# USB-C.net
KiCad netlist of a schematic drawn in Altium Designer
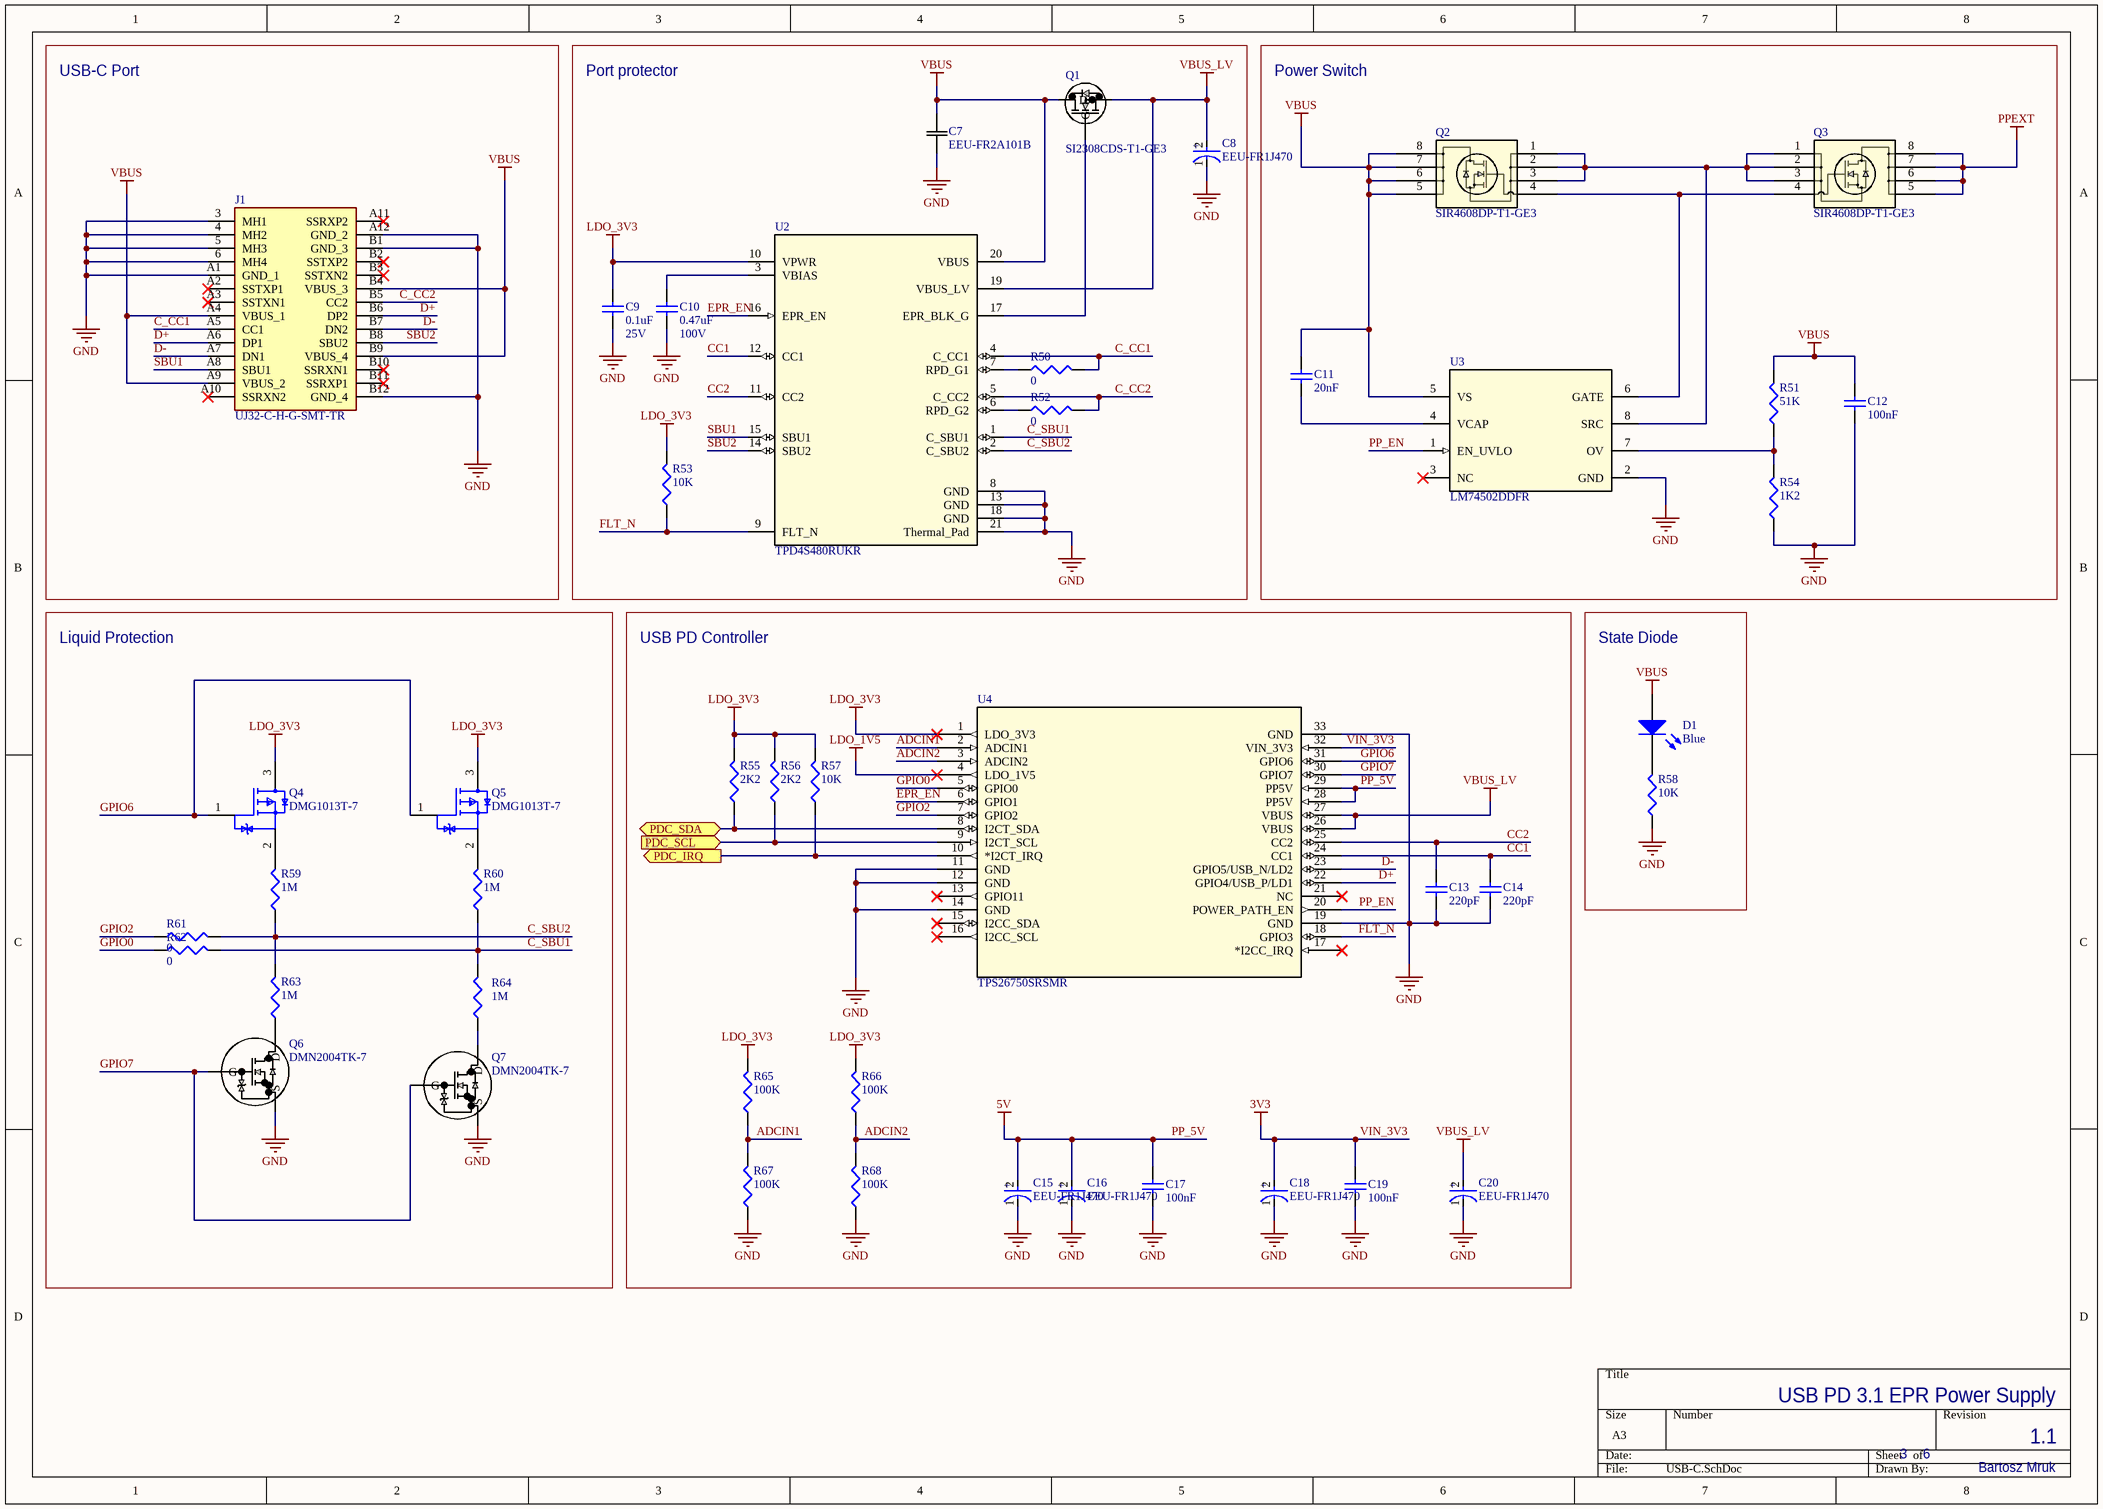
[diagram p0: USB-C.SchDoc]

(export (version "E")
  (design (tool "Eeschema 10.0.6"))
  (components
    (comp (ref "C7")
      (value "EEU-FR2A101B")
      (footprint "CAP_EEU-FR2A101B_PAN")
      (description "No Description Available")
      (fields (field (name "COPYRIGHT") "Copyright (C) 2025 Ultra Librarian. All rights reserved."))
      (libsource (lib "EEU-FR2A101B") (part "EEU-FR2A101B"))
    )
    (comp (ref "C8")
      (value "EEU-FR1J470")
      (footprint "FP-EEU-FR1J470-MFG")
      (description "CAP ALUM 47UF 20% 63V RADIAL")
      (fields (field (name "TOLERANCE") "20%") (field (name "VOLTAGE") "63V"))
      (libsource (lib "Altium Content Vault") (part "203bc49f2ac43e59fd269a8c329ed05"))
    )
    (comp (ref "C9")
      (value "25V")
      (footprint "C1206")
      (description "Capacitor (Semiconductor SIM Model)")
      (fields (field (name "ALTIUM_VALUE") "0.1uF") (field (name "PUBLISHER") "Altium Limited"))
      (libsource (lib "Miscellaneous Devices") (part "Cap Semi"))
    )
    (comp (ref "C10")
      (value "100V")
      (footprint "C1206")
      (description "Capacitor (Semiconductor SIM Model)")
      (fields (field (name "ALTIUM_VALUE") "0.47uF") (field (name "PUBLISHER") "Altium Limited"))
      (libsource (lib "Miscellaneous Devices") (part "Cap Semi"))
    )
    (comp (ref "C11")
      (value "20nF")
      (footprint "C1206")
      (description "Capacitor (Semiconductor SIM Model)")
      (fields (field (name "Comment") "at least 13V") (field (name "PUBLISHER") "Altium Limited"))
      (libsource (lib "Miscellaneous Devices") (part "Cap Semi"))
    )
    (comp (ref "C12")
      (value "100nF")
      (footprint "C1206")
      (description "Capacitor (Semiconductor SIM Model)")
      (fields (field (name "Comment") "Cap Semi") (field (name "PUBLISHER") "Altium Limited"))
      (libsource (lib "Miscellaneous Devices") (part "Cap Semi"))
    )
    (comp (ref "C13")
      (value "220pF")
      (footprint "0402")
      (description "Capacitor (Semiconductor SIM Model)")
      (fields (field (name "Comment") "Cap Semi") (field (name "PUBLISHER") "Altium Limited"))
      (libsource (lib "Miscellaneous Devices") (part "Cap Semi"))
    )
    (comp (ref "C14")
      (value "220pF")
      (footprint "0402")
      (description "Capacitor (Semiconductor SIM Model)")
      (fields (field (name "Comment") "Cap Semi") (field (name "PUBLISHER") "Altium Limited"))
      (libsource (lib "Miscellaneous Devices") (part "Cap Semi"))
    )
    (comp (ref "C15")
      (value "EEU-FR1J470")
      (footprint "FP-EEU-FR1J470-MFG")
      (description "CAP ALUM 47UF 20% 63V RADIAL")
      (fields (field (name "TOLERANCE") "20%") (field (name "VOLTAGE") "63V"))
      (libsource (lib "Altium Content Vault") (part "203bc49f2ac43e59fd269a8c329ed05"))
    )
    (comp (ref "C16")
      (value "EEU-FR1J470")
      (footprint "FP-EEU-FR1J470-MFG")
      (description "CAP ALUM 47UF 20% 63V RADIAL")
      (fields (field (name "TOLERANCE") "20%") (field (name "VOLTAGE") "63V"))
      (libsource (lib "Altium Content Vault") (part "203bc49f2ac43e59fd269a8c329ed05"))
    )
    (comp (ref "C17")
      (value "100nF")
      (footprint "C1206")
      (description "Capacitor (Semiconductor SIM Model)")
      (fields (field (name "Comment") "Cap Semi") (field (name "PUBLISHER") "Altium Limited"))
      (libsource (lib "Miscellaneous Devices") (part "Cap Semi"))
    )
    (comp (ref "C18")
      (value "EEU-FR1J470")
      (footprint "FP-EEU-FR1J470-MFG")
      (description "CAP ALUM 47UF 20% 63V RADIAL")
      (fields (field (name "TOLERANCE") "20%") (field (name "VOLTAGE") "63V"))
      (libsource (lib "Altium Content Vault") (part "203bc49f2ac43e59fd269a8c329ed05"))
    )
    (comp (ref "C19")
      (value "100nF")
      (footprint "C1206")
      (description "Capacitor (Semiconductor SIM Model)")
      (fields (field (name "Comment") "Cap Semi") (field (name "PUBLISHER") "Altium Limited"))
      (libsource (lib "Miscellaneous Devices") (part "Cap Semi"))
    )
    (comp (ref "C20")
      (value "EEU-FR1J470")
      (footprint "FP-EEU-FR1J470-MFG")
      (description "CAP ALUM 47UF 20% 63V RADIAL")
      (fields (field (name "TOLERANCE") "20%") (field (name "VOLTAGE") "63V"))
      (libsource (lib "Altium Content Vault") (part "203bc49f2ac43e59fd269a8c329ed05"))
    )
    (comp (ref "D1")
      (value "Blue")
      (footprint "3.2X1.6X1.1")
      (description "Typical RED, GREEN, YELLOW, AMBER GaAs LED")
      (fields (field (name "PUBLISHER") "Altium Limited"))
      (libsource (lib "Miscellaneous Devices") (part "LED2"))
    )
    (comp (ref "J1")
      (value "UJ32-C-H-G-SMT-TR")
      (footprint "UJ32CHGSMTTR")
      (fields (field (name "MOUSER PART NUMBER") "179-UJ32CHGSMTTR"))
      (libsource (lib "UJ32-C-H-G-SMT-TR") (part "UJ32-C-H-G-SMT-TR"))
    )
    (comp (ref "Q1")
      (value "SI2308CDS-T1-GE3")
      (footprint "SOT-23_TO-236_VIS")
      (description "N-CHANNEL 60-V (D-S) MOSFET")
      (fields (field (name "COPYRIGHT") "Copyright (C) 2025 Ultra Librarian. All rights reserved."))
      (libsource (lib "SI2308CDS-T1-GE3") (part "SI2308CDS-T1-GE3"))
    )
    (comp (ref "Q2")
      (value "SIR4608DP-T1-GE3")
      (footprint "POWERPAK_SO-8_SINGLE_VIS")
      (description "N-CHANNEL 60-V (D-S) MOSFET")
      (fields (field (name "COPYRIGHT") "Copyright (C) 2025 Ultra Librarian. All rights reserved."))
      (libsource (lib "SIR4608DP-T1-GE3") (part "SIR4608DP-T1-GE3"))
    )
    (comp (ref "Q3")
      (value "SIR4608DP-T1-GE3")
      (footprint "POWERPAK_SO-8_SINGLE_VIS")
      (description "N-CHANNEL 60-V (D-S) MOSFET")
      (fields (field (name "COPYRIGHT") "Copyright (C) 2025 Ultra Librarian. All rights reserved."))
      (libsource (lib "SIR4608DP-T1-GE3") (part "SIR4608DP-T1-GE3"))
    )
    (comp (ref "Q4")
      (value "DMG1013T-7")
      (footprint "FP-SOT523-IPC_A")
      (description "MOSFET P-CH 20V 0.46A SOT-523")
      (libsource (lib "Altium Content Vault") (part "d2c0d31e441d0c4ace7f3b05f74b3be"))
    )
    (comp (ref "Q5")
      (value "DMG1013T-7")
      (footprint "FP-SOT523-IPC_A")
      (description "MOSFET P-CH 20V 0.46A SOT-523")
      (libsource (lib "Altium Content Vault") (part "d2c0d31e441d0c4ace7f3b05f74b3be"))
    )
    (comp (ref "Q6")
      (value "DMN2004TK-7")
      (footprint "SOT523_DMN2004_DIO")
      (description "Description")
      (fields (field (name "COPYRIGHT") "Copyright (C) 2025 Ultra Librarian. All rights reserved."))
      (libsource (lib "DMN2004TK-7") (part "DMN2004TK-7"))
    )
    (comp (ref "Q7")
      (value "DMN2004TK-7")
      (footprint "SOT523_DMN2004_DIO")
      (description "Description")
      (fields (field (name "COPYRIGHT") "Copyright (C) 2025 Ultra Librarian. All rights reserved."))
      (libsource (lib "DMN2004TK-7") (part "DMN2004TK-7"))
    )
    (comp (ref "R50")
      (value "0")
      (footprint "J1-0603")
      (description "Resistor")
      (fields (field (name "Comment") "Res3") (field (name "PUBLISHER") "Altium Limited"))
      (libsource (lib "Miscellaneous Devices") (part "Res3"))
    )
    (comp (ref "R51")
      (value "51K")
      (footprint "J1-0603")
      (description "Resistor")
      (fields (field (name "Comment") "Res3") (field (name "PUBLISHER") "Altium Limited"))
      (libsource (lib "Miscellaneous Devices") (part "Res3"))
    )
    (comp (ref "R52")
      (value "0")
      (footprint "J1-0603")
      (description "Resistor")
      (fields (field (name "Comment") "Res3") (field (name "PUBLISHER") "Altium Limited"))
      (libsource (lib "Miscellaneous Devices") (part "Res3"))
    )
    (comp (ref "R53")
      (value "10K")
      (footprint "J1-0603")
      (description "Resistor")
      (fields (field (name "Comment") "Res3") (field (name "PUBLISHER") "Altium Limited"))
      (libsource (lib "Miscellaneous Devices") (part "Res3"))
    )
    (comp (ref "R54")
      (value "1K2")
      (footprint "J1-0603")
      (description "Resistor")
      (fields (field (name "Comment") "Res3") (field (name "PUBLISHER") "Altium Limited"))
      (libsource (lib "Miscellaneous Devices") (part "Res3"))
    )
    (comp (ref "R55")
      (value "2K2")
      (footprint "J1-0603")
      (description "Resistor")
      (fields (field (name "Comment") "Res3") (field (name "PUBLISHER") "Altium Limited"))
      (libsource (lib "Miscellaneous Devices") (part "Res3"))
    )
    (comp (ref "R56")
      (value "2K2")
      (footprint "J1-0603")
      (description "Resistor")
      (fields (field (name "Comment") "Res3") (field (name "PUBLISHER") "Altium Limited"))
      (libsource (lib "Miscellaneous Devices") (part "Res3"))
    )
    (comp (ref "R57")
      (value "10K")
      (footprint "J1-0603")
      (description "Resistor")
      (fields (field (name "Comment") "Res3") (field (name "PUBLISHER") "Altium Limited"))
      (libsource (lib "Miscellaneous Devices") (part "Res3"))
    )
    (comp (ref "R58")
      (value "10K")
      (footprint "J1-0603")
      (description "Resistor")
      (fields (field (name "Comment") "Res3") (field (name "PUBLISHER") "Altium Limited"))
      (libsource (lib "Miscellaneous Devices") (part "Res3"))
    )
    (comp (ref "R59")
      (value "1M")
      (footprint "J1-0603")
      (description "Resistor")
      (fields (field (name "Comment") "Res3") (field (name "PUBLISHER") "Altium Limited"))
      (libsource (lib "Miscellaneous Devices") (part "Res3"))
    )
    (comp (ref "R60")
      (value "1M")
      (footprint "J1-0603")
      (description "Resistor")
      (fields (field (name "Comment") "Res3") (field (name "PUBLISHER") "Altium Limited"))
      (libsource (lib "Miscellaneous Devices") (part "Res3"))
    )
    (comp (ref "R61")
      (value "0")
      (footprint "J1-0603")
      (description "Resistor")
      (fields (field (name "Comment") "Res3") (field (name "PUBLISHER") "Altium Limited"))
      (libsource (lib "Miscellaneous Devices") (part "Res3"))
    )
    (comp (ref "R62")
      (value "0")
      (footprint "J1-0603")
      (description "Resistor")
      (fields (field (name "Comment") "Res3") (field (name "PUBLISHER") "Altium Limited"))
      (libsource (lib "Miscellaneous Devices") (part "Res3"))
    )
    (comp (ref "R63")
      (value "1M")
      (footprint "J1-0603")
      (description "Resistor")
      (fields (field (name "Comment") "Res3") (field (name "PUBLISHER") "Altium Limited"))
      (libsource (lib "Miscellaneous Devices") (part "Res3"))
    )
    (comp (ref "R64")
      (value "1M")
      (footprint "J1-0603")
      (description "Resistor")
      (fields (field (name "Comment") "Res3") (field (name "PUBLISHER") "Altium Limited"))
      (libsource (lib "Miscellaneous Devices") (part "Res3"))
    )
    (comp (ref "R65")
      (value "100K")
      (footprint "J1-0603")
      (description "Resistor")
      (fields (field (name "Comment") "Res3") (field (name "PUBLISHER") "Altium Limited"))
      (libsource (lib "Miscellaneous Devices") (part "Res3"))
    )
    (comp (ref "R66")
      (value "100K")
      (footprint "J1-0603")
      (description "Resistor")
      (fields (field (name "Comment") "Res3") (field (name "PUBLISHER") "Altium Limited"))
      (libsource (lib "Miscellaneous Devices") (part "Res3"))
    )
    (comp (ref "R67")
      (value "100K")
      (footprint "J1-0603")
      (description "Resistor")
      (fields (field (name "Comment") "Res3") (field (name "PUBLISHER") "Altium Limited"))
      (libsource (lib "Miscellaneous Devices") (part "Res3"))
    )
    (comp (ref "R68")
      (value "100K")
      (footprint "J1-0603")
      (description "Resistor")
      (fields (field (name "Comment") "Res3") (field (name "PUBLISHER") "Altium Limited"))
      (libsource (lib "Miscellaneous Devices") (part "Res3"))
    )
    (comp (ref "U2")
      (value "TPD4S480RUKR")
      (footprint "RUK0020B-IPC_A")
      (fields (field (name "COPYRIGHT") "Copyright (C) 2025 Ultra Librarian. All rights reserved."))
      (libsource (lib "TPD4S480RUKR") (part "TPD4S480RUKR"))
    )
    (comp (ref "U3")
      (value "LM74502DDFR")
      (footprint "DDF0008A-IPC_A")
      (description "3.2-V to 65-V industrial RPP controller with load disconnect and OVP 8-SOT-23-THIN -40 to 125")
      (fields (field (name "COPYRIGHT") "Copyright (C) 2025 Ultra Librarian. All rights reserved."))
      (libsource (lib "LM74502DDFR") (part "LM74502DDFR"))
    )
    (comp (ref "U4")
      (value "TPS26750SRSMR")
      (footprint "VQFN32_RSM_TEX")
      (fields (field (name "COPYRIGHT") "Copyright (C) 2025 Ultra Librarian. All rights reserved."))
      (libsource (lib "TPS26750SRSMR") (part "TPS26750SRSMR"))
    )
  )
  (nets
    (net (code "1") (name "/ADCIN1") (class "Default")
      (node (ref "R65") (pin "1") (pinfunction "1_1") (pintype "passive"))
      (node (ref "R67") (pin "2") (pinfunction "2_2") (pintype "passive"))
      (node (ref "U4") (pin "2") (pinfunction "ADCIN1_2") (pintype "input"))
    )
    (net (code "2") (name "/ADCIN2") (class "Default")
      (node (ref "R66") (pin "1") (pinfunction "1_1") (pintype "passive"))
      (node (ref "R68") (pin "2") (pinfunction "2_2") (pintype "passive"))
      (node (ref "U4") (pin "3") (pinfunction "ADCIN2_3") (pintype "input"))
    )
    (net (code "3") (name "/CC1") (class "Default")
      (node (ref "C14") (pin "2") (pinfunction "2_2") (pintype "passive"))
      (node (ref "U2") (pin "12") (pinfunction "CC1_12") (pintype "bidirectional"))
      (node (ref "U4") (pin "24") (pinfunction "CC1_24") (pintype "bidirectional"))
    )
    (net (code "4") (name "/CC2") (class "Default")
      (node (ref "C13") (pin "2") (pinfunction "2_2") (pintype "passive"))
      (node (ref "U2") (pin "11") (pinfunction "CC2_11") (pintype "bidirectional"))
      (node (ref "U4") (pin "25") (pinfunction "CC2_25") (pintype "bidirectional"))
    )
    (net (code "5") (name "/C_CC1") (class "Default")
      (node (ref "J1") (pin "A5") (pinfunction "CC1_A5") (pintype "passive"))
      (node (ref "R50") (pin "2") (pinfunction "2_2") (pintype "passive"))
      (node (ref "U2") (pin "4") (pinfunction "C_CC1_4") (pintype "bidirectional"))
    )
    (net (code "6") (name "/C_CC2") (class "Default")
      (node (ref "J1") (pin "B5") (pinfunction "CC2_B5") (pintype "passive"))
      (node (ref "R52") (pin "2") (pinfunction "2_2") (pintype "passive"))
      (node (ref "U2") (pin "5") (pinfunction "C_CC2_5") (pintype "bidirectional"))
    )
    (net (code "7") (name "/C_SBU1") (class "Default")
      (node (ref "R60") (pin "1") (pinfunction "1_1") (pintype "passive"))
      (node (ref "R62") (pin "2") (pinfunction "2_2") (pintype "passive"))
      (node (ref "R64") (pin "2") (pinfunction "2_2") (pintype "passive"))
      (node (ref "U2") (pin "1") (pinfunction "C_SBU1_1") (pintype "bidirectional"))
    )
    (net (code "8") (name "/C_SBU2") (class "Default")
      (node (ref "R59") (pin "1") (pinfunction "1_1") (pintype "passive"))
      (node (ref "R61") (pin "2") (pinfunction "2_2") (pintype "passive"))
      (node (ref "R63") (pin "2") (pinfunction "2_2") (pintype "passive"))
      (node (ref "U2") (pin "2") (pinfunction "C_SBU2_2") (pintype "bidirectional"))
    )
    (net (code "9") (name "/D+") (class "Default")
      (node (ref "J1") (pin "A6") (pinfunction "DP1_A6") (pintype "passive"))
      (node (ref "J1") (pin "B6") (pinfunction "DP2_B6") (pintype "passive"))
      (node (ref "U4") (pin "22") (pinfunction "GPIO4/USB_P/LD1_22") (pintype "bidirectional"))
    )
    (net (code "10") (name "/D-") (class "Default")
      (node (ref "J1") (pin "A7") (pinfunction "DN1_A7") (pintype "passive"))
      (node (ref "J1") (pin "B7") (pinfunction "DN2_B7") (pintype "passive"))
      (node (ref "U4") (pin "23") (pinfunction "GPIO5/USB_N/LD2_23") (pintype "bidirectional"))
    )
    (net (code "11") (name "/EPR_EN") (class "Default")
      (node (ref "U2") (pin "16") (pinfunction "EPR_EN_16") (pintype "input"))
      (node (ref "U4") (pin "6") (pinfunction "GPIO1_6") (pintype "bidirectional"))
    )
    (net (code "12") (name "/FLT_N") (class "Default")
      (node (ref "R53") (pin "1") (pinfunction "1_1") (pintype "passive"))
      (node (ref "U2") (pin "9") (pinfunction "FLT_N_9") (pintype "open_collector"))
      (node (ref "U4") (pin "18") (pinfunction "GPIO3_18") (pintype "bidirectional"))
    )
    (net (code "13") (name "/GPIO0") (class "Default")
      (node (ref "R62") (pin "1") (pinfunction "1_1") (pintype "passive"))
      (node (ref "U4") (pin "5") (pinfunction "GPIO0_5") (pintype "bidirectional"))
    )
    (net (code "14") (name "/GPIO2") (class "Default")
      (node (ref "R61") (pin "1") (pinfunction "1_1") (pintype "passive"))
      (node (ref "U4") (pin "7") (pinfunction "GPIO2_7") (pintype "bidirectional"))
    )
    (net (code "15") (name "/GPIO6") (class "Default")
      (node (ref "Q4") (pin "1") (pinfunction "G_1") (pintype "passive"))
      (node (ref "Q5") (pin "1") (pinfunction "G_1") (pintype "passive"))
      (node (ref "U4") (pin "31") (pinfunction "GPIO6_31") (pintype "bidirectional"))
    )
    (net (code "16") (name "/GPIO7") (class "Default")
      (node (ref "Q6") (pin "1") (pinfunction "G_1") (pintype "passive"))
      (node (ref "Q7") (pin "1") (pinfunction "G_1") (pintype "passive"))
      (node (ref "U4") (pin "30") (pinfunction "GPIO7_30") (pintype "bidirectional"))
    )
    (net (code "17") (name "/PDC_IRQ") (class "Default")
      (node (ref "R57") (pin "1") (pinfunction "1_1") (pintype "passive"))
      (node (ref "U4") (pin "10") (pinfunction "*I2CT_IRQ_10") (pintype "output"))
    )
    (net (code "18") (name "/PDC_SCL") (class "Default")
      (node (ref "R56") (pin "1") (pinfunction "1_1") (pintype "passive"))
      (node (ref "U4") (pin "9") (pinfunction "I2CT_SCL_9") (pintype "input"))
    )
    (net (code "19") (name "/PDC_SDA") (class "Default")
      (node (ref "R55") (pin "1") (pinfunction "1_1") (pintype "passive"))
      (node (ref "U4") (pin "8") (pinfunction "I2CT_SDA_8") (pintype "bidirectional"))
    )
    (net (code "20") (name "/PP_EN") (class "Default")
      (node (ref "U3") (pin "1") (pinfunction "EN_UVLO_1") (pintype "input"))
      (node (ref "U4") (pin "20") (pinfunction "POWER_PATH_EN_20") (pintype "output"))
    )
    (net (code "21") (name "/SBU1") (class "Default")
      (node (ref "J1") (pin "A8") (pinfunction "SBU1_A8") (pintype "passive"))
      (node (ref "U2") (pin "15") (pinfunction "SBU1_15") (pintype "bidirectional"))
    )
    (net (code "22") (name "/SBU2") (class "Default")
      (node (ref "J1") (pin "B8") (pinfunction "SBU2_B8") (pintype "passive"))
      (node (ref "U2") (pin "14") (pinfunction "SBU2_14") (pintype "bidirectional"))
    )
    (net (code "23") (name "3V3") (class "Default")
      (node (ref "C18") (pin "2") (pinfunction "A_2") (pintype "passive"))
      (node (ref "C19") (pin "2") (pinfunction "2_2") (pintype "passive"))
      (node (ref "U4") (pin "32") (pinfunction "VIN_3V3_32") (pintype "input"))
    )
    (net (code "24") (name "5V") (class "Default")
      (node (ref "C15") (pin "2") (pinfunction "A_2") (pintype "passive"))
      (node (ref "C16") (pin "2") (pinfunction "A_2") (pintype "passive"))
      (node (ref "C17") (pin "2") (pinfunction "2_2") (pintype "passive"))
      (node (ref "U4") (pin "28") (pinfunction "PP5V_28") (pintype "input"))
      (node (ref "U4") (pin "29") (pinfunction "PP5V_29") (pintype "input"))
    )
    (net (code "25") (name "GND") (class "Default")
      (node (ref "C10") (pin "1") (pinfunction "1_1") (pintype "passive"))
      (node (ref "C12") (pin "1") (pinfunction "1_1") (pintype "passive"))
      (node (ref "C13") (pin "1") (pinfunction "1_1") (pintype "passive"))
      (node (ref "C14") (pin "1") (pinfunction "1_1") (pintype "passive"))
      (node (ref "C15") (pin "1") (pinfunction "C_1") (pintype "passive"))
      (node (ref "C16") (pin "1") (pinfunction "C_1") (pintype "passive"))
      (node (ref "C17") (pin "1") (pinfunction "1_1") (pintype "passive"))
      (node (ref "C18") (pin "1") (pinfunction "C_1") (pintype "passive"))
      (node (ref "C19") (pin "1") (pinfunction "1_1") (pintype "passive"))
      (node (ref "C20") (pin "1") (pinfunction "C_1") (pintype "passive"))
      (node (ref "C7") (pin "2") (pinfunction "2_2") (pintype "passive"))
      (node (ref "C8") (pin "1") (pinfunction "C_1") (pintype "passive"))
      (node (ref "C9") (pin "1") (pinfunction "1_1") (pintype "passive"))
      (node (ref "J1") (pin "3") (pinfunction "MH1_3") (pintype "passive"))
      (node (ref "J1") (pin "4") (pinfunction "MH2_4") (pintype "passive"))
      (node (ref "J1") (pin "5") (pinfunction "MH3_5") (pintype "passive"))
      (node (ref "J1") (pin "6") (pinfunction "MH4_6") (pintype "passive"))
      (node (ref "J1") (pin "A1") (pinfunction "GND_1_A1") (pintype "passive"))
      (node (ref "J1") (pin "A12") (pinfunction "GND_2_A12") (pintype "passive"))
      (node (ref "J1") (pin "B1") (pinfunction "GND_3_B1") (pintype "passive"))
      (node (ref "J1") (pin "B12") (pinfunction "GND_4_B12") (pintype "passive"))
      (node (ref "Q6") (pin "3") (pinfunction "S_3") (pintype "passive"))
      (node (ref "Q7") (pin "3") (pinfunction "S_3") (pintype "passive"))
      (node (ref "R54") (pin "1") (pinfunction "1_1") (pintype "passive"))
      (node (ref "R58") (pin "1") (pinfunction "1_1") (pintype "passive"))
      (node (ref "R67") (pin "1") (pinfunction "1_1") (pintype "passive"))
      (node (ref "R68") (pin "1") (pinfunction "1_1") (pintype "passive"))
      (node (ref "U2") (pin "13") (pinfunction "GND_13") (pintype "power_in"))
      (node (ref "U2") (pin "18") (pinfunction "GND_18") (pintype "power_in"))
      (node (ref "U2") (pin "21") (pinfunction "Thermal_Pad_21") (pintype "passive"))
      (node (ref "U2") (pin "8") (pinfunction "GND_8") (pintype "power_in"))
      (node (ref "U3") (pin "2") (pinfunction "GND_2") (pintype "power_in"))
      (node (ref "U4") (pin "11") (pinfunction "GND_11") (pintype "power_in"))
      (node (ref "U4") (pin "12") (pinfunction "GND_12") (pintype "power_in"))
      (node (ref "U4") (pin "14") (pinfunction "GND_14") (pintype "power_in"))
      (node (ref "U4") (pin "19") (pinfunction "GND_19") (pintype "power_in"))
      (node (ref "U4") (pin "33") (pinfunction "GND_33") (pintype "power_in"))
    )
    (net (code "26") (name "LDO_1V5") (class "Default")
      (node (ref "U4") (pin "4") (pinfunction "LDO_1V5_4") (pintype "output"))
    )
    (net (code "27") (name "LDO_3V3") (class "Default")
      (node (ref "C9") (pin "2") (pinfunction "2_2") (pintype "passive"))
      (node (ref "Q4") (pin "3") (pinfunction "D_3") (pintype "passive"))
      (node (ref "Q5") (pin "3") (pinfunction "D_3") (pintype "passive"))
      (node (ref "R53") (pin "2") (pinfunction "2_2") (pintype "passive"))
      (node (ref "R55") (pin "2") (pinfunction "2_2") (pintype "passive"))
      (node (ref "R56") (pin "2") (pinfunction "2_2") (pintype "passive"))
      (node (ref "R57") (pin "2") (pinfunction "2_2") (pintype "passive"))
      (node (ref "R65") (pin "2") (pinfunction "2_2") (pintype "passive"))
      (node (ref "R66") (pin "2") (pinfunction "2_2") (pintype "passive"))
      (node (ref "U2") (pin "10") (pinfunction "VPWR_10") (pintype "power_in"))
      (node (ref "U4") (pin "1") (pinfunction "LDO_3V3_1") (pintype "output"))
    )
    (net (code "28") (name "Net-(D1-K)") (class "Default")
      (node (ref "D1") (pin "2") (pinfunction "K_2") (pintype "passive"))
      (node (ref "R58") (pin "2") (pinfunction "2_2") (pintype "passive"))
    )
    (net (code "29") (name "Net-(Q1-G)") (class "Default")
      (node (ref "Q1") (pin "1") (pinfunction "G_1") (pintype "passive"))
      (node (ref "U2") (pin "17") (pinfunction "EPR_BLK_G_17") (pintype "passive"))
    )
    (net (code "30") (name "Net-(Q4-S)") (class "Default")
      (node (ref "Q4") (pin "2") (pinfunction "S_2") (pintype "passive"))
      (node (ref "R59") (pin "2") (pinfunction "2_2") (pintype "passive"))
    )
    (net (code "31") (name "Net-(Q5-S)") (class "Default")
      (node (ref "Q5") (pin "2") (pinfunction "S_2") (pintype "passive"))
      (node (ref "R60") (pin "2") (pinfunction "2_2") (pintype "passive"))
    )
    (net (code "32") (name "Net-(Q6-D)") (class "Default")
      (node (ref "Q6") (pin "2") (pinfunction "D_2") (pintype "passive"))
      (node (ref "R63") (pin "1") (pinfunction "1_1") (pintype "passive"))
    )
    (net (code "33") (name "Net-(Q7-D)") (class "Default")
      (node (ref "Q7") (pin "2") (pinfunction "D_2") (pintype "passive"))
      (node (ref "R64") (pin "1") (pinfunction "1_1") (pintype "passive"))
    )
    (net (code "34") (name "Net-(U2-RPD_G1)") (class "Default")
      (node (ref "R50") (pin "1") (pinfunction "1_1") (pintype "passive"))
      (node (ref "U2") (pin "7") (pinfunction "RPD_G1_7") (pintype "bidirectional"))
    )
    (net (code "35") (name "Net-(U2-RPD_G2)") (class "Default")
      (node (ref "R52") (pin "1") (pinfunction "1_1") (pintype "passive"))
      (node (ref "U2") (pin "6") (pinfunction "RPD_G2_6") (pintype "bidirectional"))
    )
    (net (code "36") (name "Net-(U2-VBIAS)") (class "Default")
      (node (ref "C10") (pin "2") (pinfunction "2_2") (pintype "passive"))
      (node (ref "U2") (pin "3") (pinfunction "VBIAS_3") (pintype "power_in"))
    )
    (net (code "37") (name "Net-(U3-GATE)") (class "Default")
      (node (ref "Q2") (pin "4") (pinfunction "4_4") (pintype "passive"))
      (node (ref "Q3") (pin "4") (pinfunction "4_4") (pintype "passive"))
      (node (ref "U3") (pin "6") (pinfunction "GATE_6") (pintype "passive"))
    )
    (net (code "38") (name "Net-(U3-OV)") (class "Default")
      (node (ref "R51") (pin "1") (pinfunction "1_1") (pintype "passive"))
      (node (ref "R54") (pin "2") (pinfunction "2_2") (pintype "passive"))
      (node (ref "U3") (pin "7") (pinfunction "OV_7") (pintype "passive"))
    )
    (net (code "39") (name "Net-(U3-SRC)") (class "Default")
      (node (ref "Q2") (pin "1") (pinfunction "1_1") (pintype "passive"))
      (node (ref "Q2") (pin "2") (pinfunction "2_2") (pintype "passive"))
      (node (ref "Q2") (pin "3") (pinfunction "3_3") (pintype "passive"))
      (node (ref "Q3") (pin "1") (pinfunction "1_1") (pintype "passive"))
      (node (ref "Q3") (pin "2") (pinfunction "2_2") (pintype "passive"))
      (node (ref "Q3") (pin "3") (pinfunction "3_3") (pintype "passive"))
      (node (ref "U3") (pin "8") (pinfunction "SRC_8") (pintype "passive"))
    )
    (net (code "40") (name "Net-(U3-VCAP)") (class "Default")
      (node (ref "C11") (pin "1") (pinfunction "1_1") (pintype "passive"))
      (node (ref "U3") (pin "4") (pinfunction "VCAP_4") (pintype "passive"))
    )
    (net (code "41") (name "PPEXT") (class "Default")
      (node (ref "Q3") (pin "5") (pinfunction "5_5") (pintype "passive"))
      (node (ref "Q3") (pin "6") (pinfunction "6_6") (pintype "passive"))
      (node (ref "Q3") (pin "7") (pinfunction "7_7") (pintype "passive"))
      (node (ref "Q3") (pin "8") (pinfunction "8_8") (pintype "passive"))
    )
    (net (code "42") (name "VBUS") (class "Default")
      (node (ref "C11") (pin "2") (pinfunction "2_2") (pintype "passive"))
      (node (ref "C12") (pin "2") (pinfunction "2_2") (pintype "passive"))
      (node (ref "C7") (pin "1") (pinfunction "1_1") (pintype "passive"))
      (node (ref "D1") (pin "1") (pinfunction "A_1") (pintype "passive"))
      (node (ref "J1") (pin "A4") (pinfunction "VBUS_1_A4") (pintype "passive"))
      (node (ref "J1") (pin "A9") (pinfunction "VBUS_2_A9") (pintype "passive"))
      (node (ref "J1") (pin "B4") (pinfunction "VBUS_3_B4") (pintype "passive"))
      (node (ref "J1") (pin "B9") (pinfunction "VBUS_4_B9") (pintype "passive"))
      (node (ref "Q1") (pin "2") (pinfunction "D_2") (pintype "passive"))
      (node (ref "Q2") (pin "5") (pinfunction "5_5") (pintype "passive"))
      (node (ref "Q2") (pin "6") (pinfunction "6_6") (pintype "passive"))
      (node (ref "Q2") (pin "7") (pinfunction "7_7") (pintype "passive"))
      (node (ref "Q2") (pin "8") (pinfunction "8_8") (pintype "passive"))
      (node (ref "R51") (pin "2") (pinfunction "2_2") (pintype "passive"))
      (node (ref "U2") (pin "20") (pinfunction "VBUS_20") (pintype "passive"))
      (node (ref "U3") (pin "5") (pinfunction "VS_5") (pintype "power_in"))
    )
    (net (code "43") (name "VBUS_LV") (class "Default")
      (node (ref "C20") (pin "2") (pinfunction "A_2") (pintype "passive"))
      (node (ref "C8") (pin "2") (pinfunction "A_2") (pintype "passive"))
      (node (ref "Q1") (pin "3") (pinfunction "S_3") (pintype "passive"))
      (node (ref "U2") (pin "19") (pinfunction "VBUS_LV_19") (pintype "passive"))
      (node (ref "U4") (pin "26") (pinfunction "VBUS_26") (pintype "bidirectional"))
      (node (ref "U4") (pin "27") (pinfunction "VBUS_27") (pintype "bidirectional"))
    )
    (net (code "44") (name "unconnected-(J1-SSRXN1-PadB10)") (class "Default")
      (node (ref "J1") (pin "B10") (pinfunction "SSRXN1_B10") (pintype "passive+no_connect"))
    )
    (net (code "45") (name "unconnected-(J1-SSRXN2-PadA10)") (class "Default")
      (node (ref "J1") (pin "A10") (pinfunction "SSRXN2_A10") (pintype "passive+no_connect"))
    )
    (net (code "46") (name "unconnected-(J1-SSRXP1-PadB11)") (class "Default")
      (node (ref "J1") (pin "B11") (pinfunction "SSRXP1_B11") (pintype "passive+no_connect"))
    )
    (net (code "47") (name "unconnected-(J1-SSRXP2-PadA11)") (class "Default")
      (node (ref "J1") (pin "A11") (pinfunction "SSRXP2_A11") (pintype "passive+no_connect"))
    )
    (net (code "48") (name "unconnected-(J1-SSTXN1-PadA3)") (class "Default")
      (node (ref "J1") (pin "A3") (pinfunction "SSTXN1_A3") (pintype "passive+no_connect"))
    )
    (net (code "49") (name "unconnected-(J1-SSTXN2-PadB3)") (class "Default")
      (node (ref "J1") (pin "B3") (pinfunction "SSTXN2_B3") (pintype "passive+no_connect"))
    )
    (net (code "50") (name "unconnected-(J1-SSTXP1-PadA2)") (class "Default")
      (node (ref "J1") (pin "A2") (pinfunction "SSTXP1_A2") (pintype "passive+no_connect"))
    )
    (net (code "51") (name "unconnected-(J1-SSTXP2-PadB2)") (class "Default")
      (node (ref "J1") (pin "B2") (pinfunction "SSTXP2_B2") (pintype "passive+no_connect"))
    )
    (net (code "52") (name "unconnected-(U3-NC-Pad3)") (class "Default")
      (node (ref "U3") (pin "3") (pinfunction "NC_3") (pintype "passive+no_connect"))
    )
    (net (code "53") (name "unconnected-(U4-*I2CC_IRQ-Pad17)") (class "Default")
      (node (ref "U4") (pin "17") (pinfunction "*I2CC_IRQ_17") (pintype "input+no_connect"))
    )
    (net (code "54") (name "unconnected-(U4-GPIO11-Pad13)") (class "Default")
      (node (ref "U4") (pin "13") (pinfunction "GPIO11_13") (pintype "output+no_connect"))
    )
    (net (code "55") (name "unconnected-(U4-I2CC_SCL-Pad16)") (class "Default")
      (node (ref "U4") (pin "16") (pinfunction "I2CC_SCL_16") (pintype "output+no_connect"))
    )
    (net (code "56") (name "unconnected-(U4-I2CC_SDA-Pad15)") (class "Default")
      (node (ref "U4") (pin "15") (pinfunction "I2CC_SDA_15") (pintype "bidirectional+no_connect"))
    )
    (net (code "57") (name "unconnected-(U4-NC-Pad21)") (class "Default")
      (node (ref "U4") (pin "21") (pinfunction "NC_21") (pintype "passive+no_connect"))
    )
  )
)
